# CCM_0018.net
KiCad netlist of a schematic drawn in EAGLE
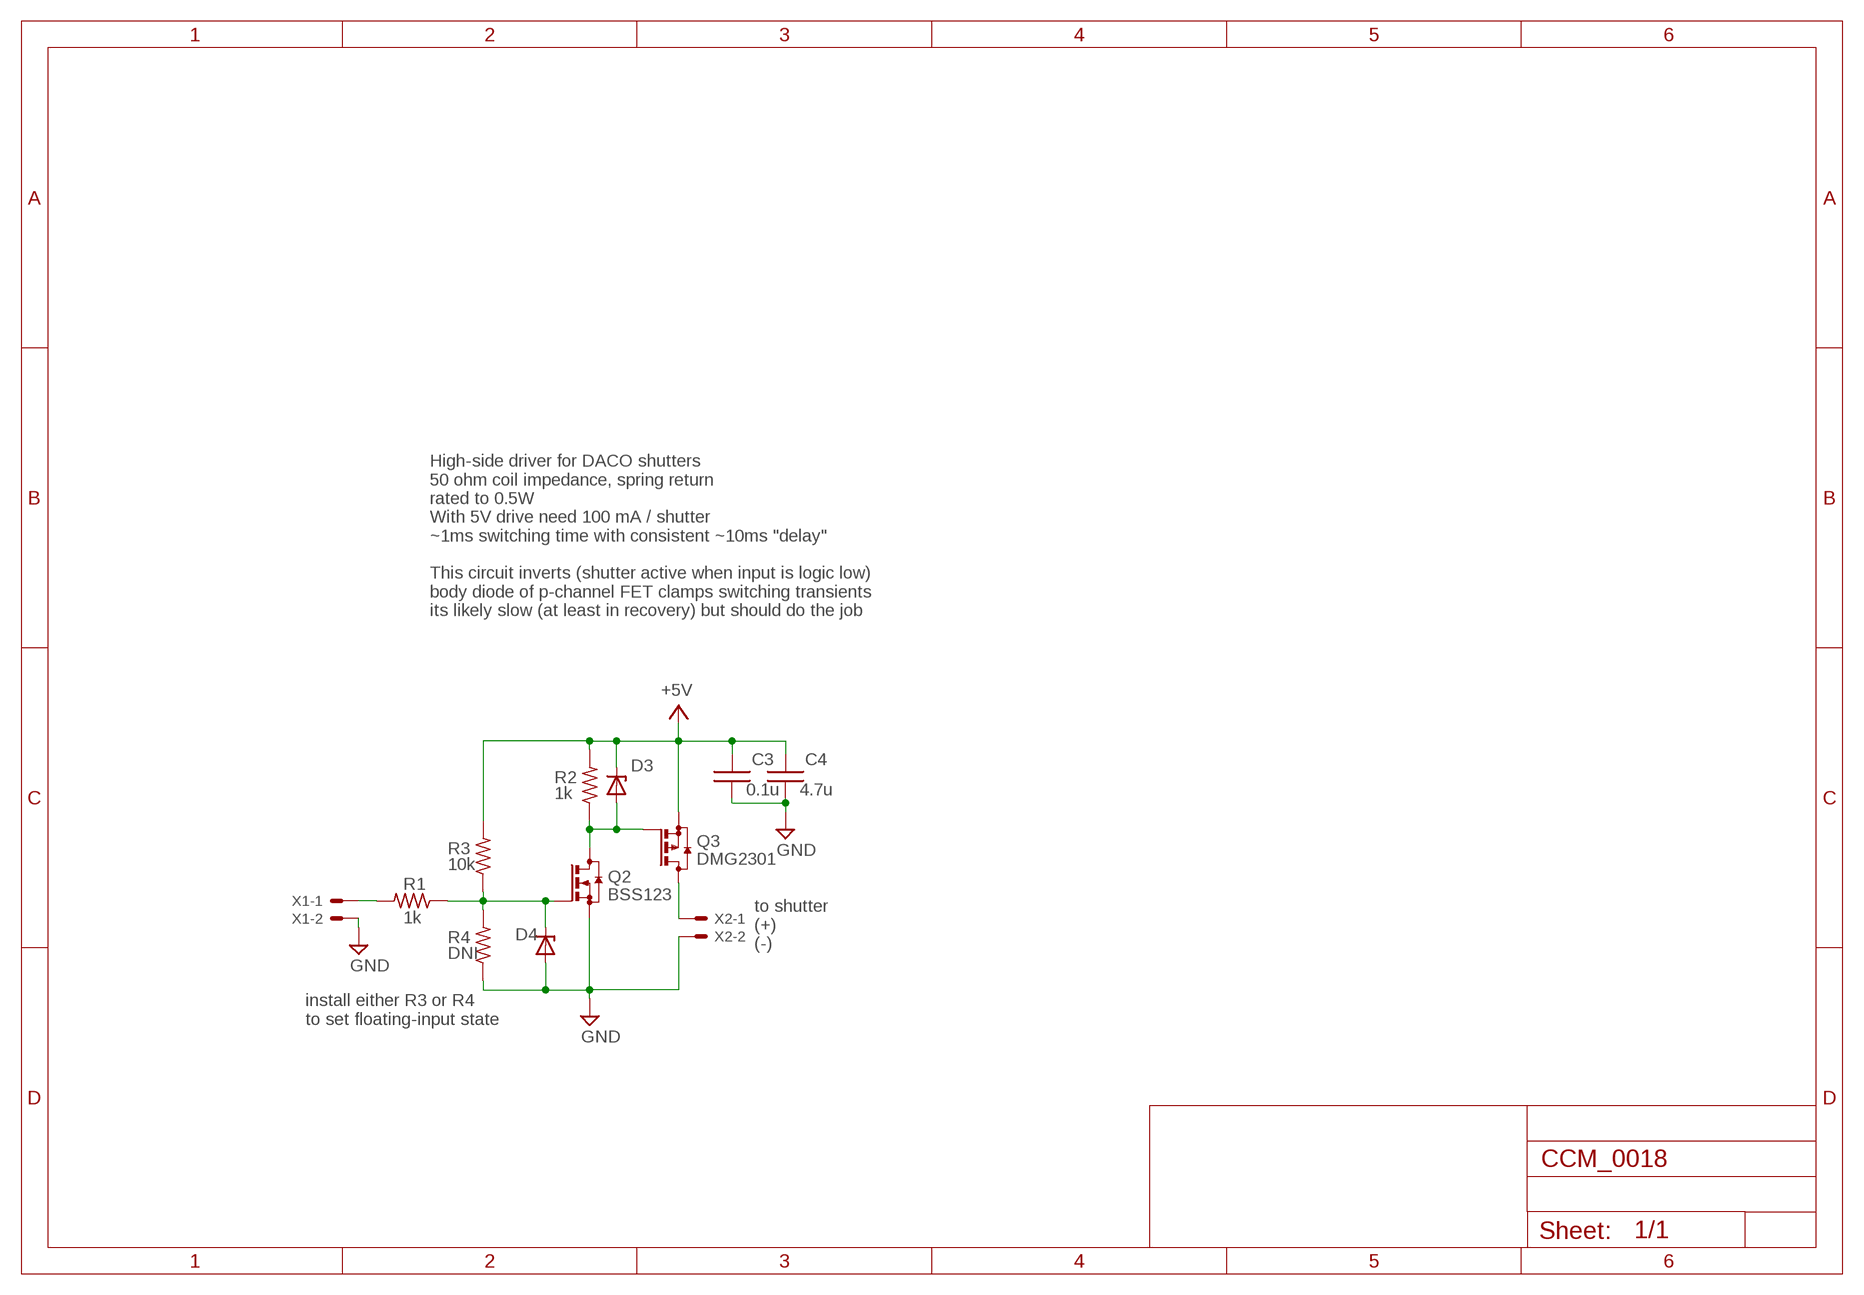
[diagram p0: schematic, sheet 1]

(export (version "E")
  (design (tool "Eeschema 10.0.6"))
  (components
    (comp (ref "C3")
      (value "0.1u")
      (footprint "eagle-import:0603")
      (libsource (lib "eagle-import") (part "CAPACITOR0603"))
    )
    (comp (ref "C4")
      (value "4.7u")
      (footprint "eagle-import:0603")
      (libsource (lib "eagle-import") (part "CAPACITOR0603"))
    )
    (comp (ref "D3")
      (value "ZENER-DIODESOT23")
      (footprint "eagle-import:SOT23")
      (libsource (lib "eagle-import") (part "ZENER-DIODESOT23"))
    )
    (comp (ref "D4")
      (value "ZENER-DIODESOT23")
      (footprint "eagle-import:SOT23")
      (libsource (lib "eagle-import") (part "ZENER-DIODESOT23"))
    )
    (comp (ref "Q2")
      (value "BSS123")
      (footprint "eagle-import:SOT23")
      (libsource (lib "eagle-import") (part "BSS123"))
    )
    (comp (ref "Q3")
      (value "DMG2301")
      (footprint "eagle-import:SOT23")
      (libsource (lib "eagle-import") (part "BSS84"))
    )
    (comp (ref "R1")
      (value "1k")
      (footprint "eagle-import:0603")
      (libsource (lib "eagle-import") (part "RESISTOR0603"))
    )
    (comp (ref "R2")
      (value "1k")
      (footprint "eagle-import:0603")
      (libsource (lib "eagle-import") (part "RESISTOR0603"))
    )
    (comp (ref "R3")
      (value "10k")
      (footprint "eagle-import:0603")
      (libsource (lib "eagle-import") (part "RESISTOR0603"))
    )
    (comp (ref "R4")
      (value "DNI")
      (footprint "eagle-import:0603")
      (libsource (lib "eagle-import") (part "RESISTOR0603"))
    )
    (comp (ref "X1")
      (value "22-23-2021")
      (footprint "eagle-import:22-23-2021")
      (fields (field (name "MF") "MOLEX"))
      (libsource (lib "eagle-import") (part "22-23-2021"))
    )
    (comp (ref "X2")
      (value "22-23-2021")
      (footprint "eagle-import:22-23-2021")
      (fields (field (name "MF") "MOLEX"))
      (libsource (lib "eagle-import") (part "22-23-2021"))
    )
  )
  (nets
    (net (code "1") (name "+5V") (class "Default")
      (node (ref "C3") (pin "1") (pinfunction "1_1") (pintype "passive"))
      (node (ref "C4") (pin "1") (pinfunction "1_1") (pintype "passive"))
      (node (ref "D3") (pin "3") (pinfunction "C_3") (pintype "passive"))
      (node (ref "Q3") (pin "2") (pinfunction "S_2") (pintype "passive"))
      (node (ref "R2") (pin "2") (pinfunction "2_2") (pintype "passive"))
      (node (ref "R3") (pin "2") (pinfunction "2_2") (pintype "passive"))
    )
    (net (code "2") (name "GND") (class "Default")
      (node (ref "C3") (pin "2") (pinfunction "2_2") (pintype "passive"))
      (node (ref "C4") (pin "2") (pinfunction "2_2") (pintype "passive"))
      (node (ref "D4") (pin "1") (pinfunction "A_1") (pintype "passive"))
      (node (ref "Q2") (pin "2") (pinfunction "S_2") (pintype "passive"))
      (node (ref "R4") (pin "1") (pinfunction "1_1") (pintype "passive"))
      (node (ref "X1") (pin "2") (pinfunction "S_2") (pintype "passive"))
      (node (ref "X2") (pin "2") (pinfunction "S_2") (pintype "passive"))
    )
    (net (code "3") (name "Net-(D3-A)") (class "Default")
      (node (ref "D3") (pin "1") (pinfunction "A_1") (pintype "passive"))
      (node (ref "Q2") (pin "3") (pinfunction "D_3") (pintype "passive"))
      (node (ref "Q3") (pin "1") (pinfunction "G_1") (pintype "passive"))
      (node (ref "R2") (pin "1") (pinfunction "1_1") (pintype "passive"))
    )
    (net (code "4") (name "Net-(D4-C)") (class "Default")
      (node (ref "D4") (pin "3") (pinfunction "C_3") (pintype "passive"))
      (node (ref "Q2") (pin "1") (pinfunction "G_1") (pintype "passive"))
      (node (ref "R1") (pin "1") (pinfunction "1_1") (pintype "passive"))
      (node (ref "R3") (pin "1") (pinfunction "1_1") (pintype "passive"))
      (node (ref "R4") (pin "2") (pinfunction "2_2") (pintype "passive"))
    )
    (net (code "5") (name "Net-(Q3-D)") (class "Default")
      (node (ref "Q3") (pin "3") (pinfunction "D_3") (pintype "passive"))
      (node (ref "X2") (pin "1") (pinfunction "S_1") (pintype "passive"))
    )
    (net (code "6") (name "Net-(X1A-S)") (class "Default")
      (node (ref "R1") (pin "2") (pinfunction "2_2") (pintype "passive"))
      (node (ref "X1") (pin "1") (pinfunction "S_1") (pintype "passive"))
    )
  )
)
